# relays.net
KiCad netlist of a schematic drawn in EAGLE
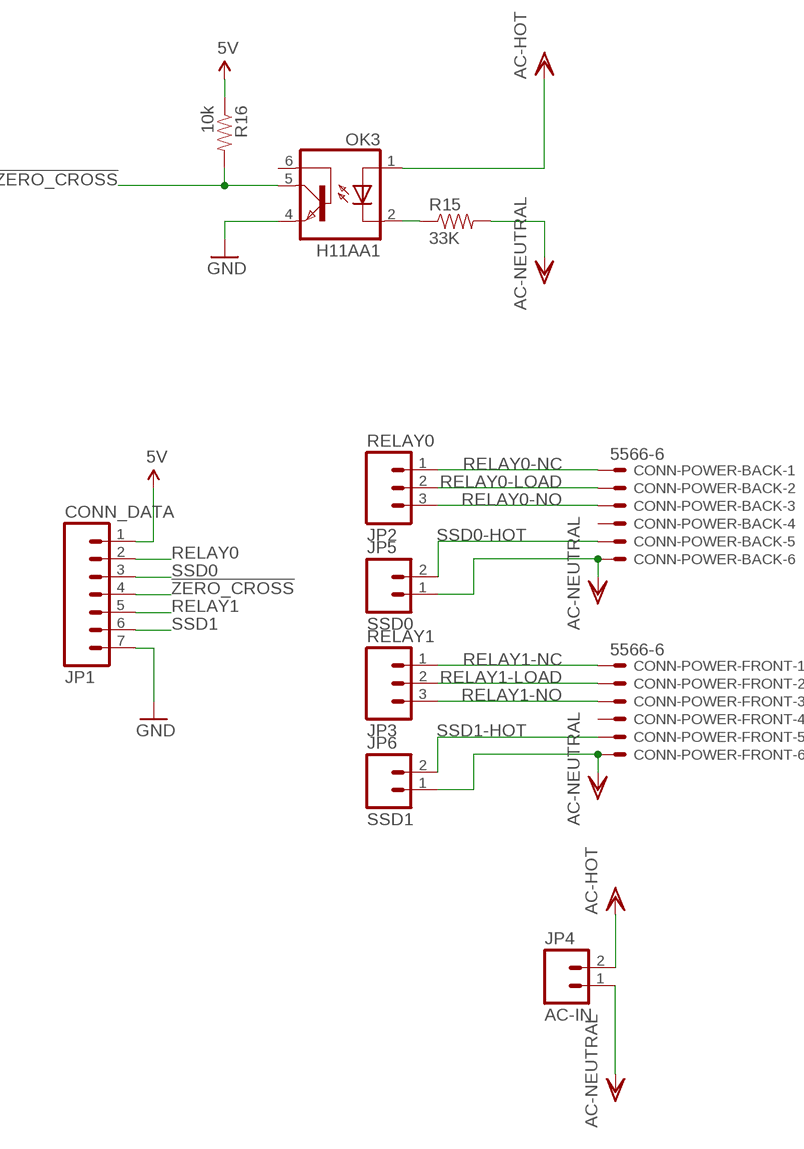
[diagram p0: schematic, sheet 1]
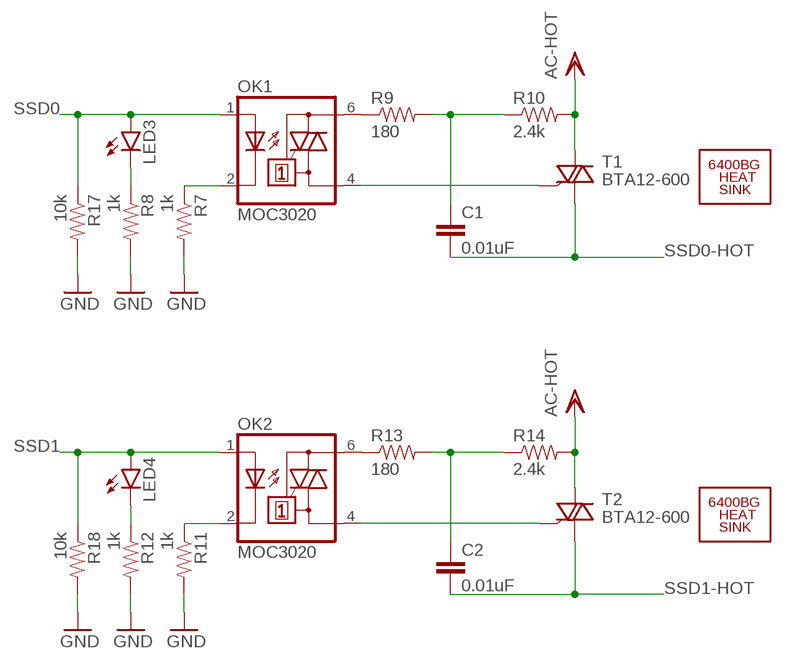
[diagram p1: schematic, sheet 2]
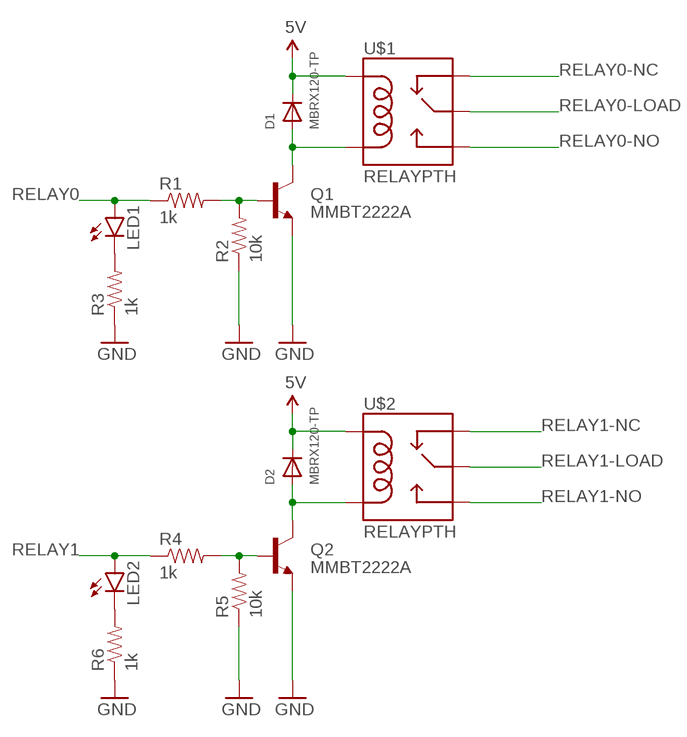
[diagram p2: schematic, sheet 3]

(export (version "E")
  (design (tool "Eeschema 10.0.6"))
  (components
    (comp (ref "CONN-POWER-BACK")
      (value "5566-6")
      (footprint "eagle-import:5566-6")
      (fields (field (name "MPN") "95566-61002"))
      (libsource (lib "eagle-import") (part "5566-6"))
    )
    (comp (ref "CONN-POWER-FRONT")
      (value "5566-6")
      (footprint "eagle-import:5566-6")
      (fields (field (name "MPN") "95566-61002"))
      (libsource (lib "eagle-import") (part "5566-6"))
    )
    (comp (ref "JP1")
      (value "CONN_DATA")
      (footprint "eagle-import:1X07_LONGPADS")
      (libsource (lib "eagle-import") (part "M07LONGPADS"))
    )
    (comp (ref "JP2")
      (value "RELAY0")
      (footprint "eagle-import:SCREWTERMINAL-5MM-3")
      (libsource (lib "eagle-import") (part "M03-SCREW-5MM"))
    )
    (comp (ref "JP3")
      (value "RELAY1")
      (footprint "eagle-import:SCREWTERMINAL-5MM-3")
      (libsource (lib "eagle-import") (part "M03-SCREW-5MM"))
    )
    (comp (ref "JP4")
      (value "AC-IN")
      (footprint "eagle-import:SCREWTERMINAL-5MM-2")
      (libsource (lib "eagle-import") (part "M025MM"))
    )
    (comp (ref "JP5")
      (value "SSD0")
      (footprint "eagle-import:SCREWTERMINAL-5MM-2")
      (libsource (lib "eagle-import") (part "M025MM"))
    )
    (comp (ref "JP6")
      (value "SSD1")
      (footprint "eagle-import:SCREWTERMINAL-5MM-2")
      (libsource (lib "eagle-import") (part "M025MM"))
    )
    (comp (ref "OK3")
      (value "H11AA1")
      (footprint "eagle-import:DIL6-SMD")
      (libsource (lib "eagle-import") (part "H11A?MS1"))
    )
    (comp (ref "R15")
      (value "33K")
      (footprint "eagle-import:0603-RES")
      (libsource (lib "eagle-import") (part "RESISTOR0603-RES"))
    )
    (comp (ref "R16")
      (value "10k")
      (footprint "eagle-import:0603-RES")
      (libsource (lib "eagle-import") (part "RESISTOR0603-RES"))
    )
    (comp (ref "D1")
      (value "MBRX120-TP")
      (footprint "eagle-import:SOD-123")
      (libsource (lib "eagle-import") (part "DIODESOD-123"))
    )
    (comp (ref "D2")
      (value "MBRX120-TP")
      (footprint "eagle-import:SOD-123")
      (libsource (lib "eagle-import") (part "DIODESOD-123"))
    )
    (comp (ref "LED1")
      (value "LED0603")
      (footprint "eagle-import:LED-0603")
      (libsource (lib "eagle-import") (part "LED0603"))
    )
    (comp (ref "LED2")
      (value "LED0603")
      (footprint "eagle-import:LED-0603")
      (libsource (lib "eagle-import") (part "LED0603"))
    )
    (comp (ref "Q1")
      (value "MMBT2222A")
      (footprint "eagle-import:SOT23-3")
      (libsource (lib "eagle-import") (part "TRANSISTOR_NPNMMBT2222A"))
    )
    (comp (ref "Q2")
      (value "MMBT2222A")
      (footprint "eagle-import:SOT23-3")
      (libsource (lib "eagle-import") (part "TRANSISTOR_NPNMMBT2222A"))
    )
    (comp (ref "R1")
      (value "1k")
      (footprint "eagle-import:0603-RES")
      (libsource (lib "eagle-import") (part "RESISTOR0603-RES"))
    )
    (comp (ref "R2")
      (value "10k")
      (footprint "eagle-import:0603-RES")
      (libsource (lib "eagle-import") (part "RESISTOR0603-RES"))
    )
    (comp (ref "R3")
      (value "1k")
      (footprint "eagle-import:0603-RES")
      (libsource (lib "eagle-import") (part "RESISTOR0603-RES"))
    )
    (comp (ref "R4")
      (value "1k")
      (footprint "eagle-import:0603-RES")
      (libsource (lib "eagle-import") (part "RESISTOR0603-RES"))
    )
    (comp (ref "R5")
      (value "10k")
      (footprint "eagle-import:0603-RES")
      (libsource (lib "eagle-import") (part "RESISTOR0603-RES"))
    )
    (comp (ref "R6")
      (value "1k")
      (footprint "eagle-import:0603-RES")
      (libsource (lib "eagle-import") (part "RESISTOR0603-RES"))
    )
    (comp (ref "U$1")
      (value "RELAYPTH")
      (footprint "eagle-import:RELAY-G5Q")
      (libsource (lib "eagle-import") (part "RELAYPTH"))
    )
    (comp (ref "U$2")
      (value "RELAYPTH")
      (footprint "eagle-import:RELAY-G5Q")
      (libsource (lib "eagle-import") (part "RELAYPTH"))
    )
    (comp (ref "C1")
      (value "0.01uF")
      (footprint "eagle-import:0603-CAP")
      (libsource (lib "eagle-import") (part "CAP0603-CAP"))
    )
    (comp (ref "C2")
      (value "0.01uF")
      (footprint "eagle-import:0603-CAP")
      (libsource (lib "eagle-import") (part "CAP0603-CAP"))
    )
    (comp (ref "LED3")
      (value "LED0603")
      (footprint "eagle-import:LED-0603")
      (libsource (lib "eagle-import") (part "LED0603"))
    )
    (comp (ref "LED4")
      (value "LED0603")
      (footprint "eagle-import:LED-0603")
      (libsource (lib "eagle-import") (part "LED0603"))
    )
    (comp (ref "OK1")
      (value "MOC3020")
      (footprint "eagle-import:DIL6-SMD")
      (fields (field (name "MF") "FAIRCHILD SEMICONDUCTOR") (field (name "MPN") "MOC3031SM"))
      (libsource (lib "eagle-import") (part "MOC30S31"))
    )
    (comp (ref "OK2")
      (value "MOC3020")
      (footprint "eagle-import:DIL6-SMD")
      (fields (field (name "MF") "FAIRCHILD SEMICONDUCTOR") (field (name "MPN") "MOC3031SM"))
      (libsource (lib "eagle-import") (part "MOC30S31"))
    )
    (comp (ref "R7")
      (value "1k")
      (footprint "eagle-import:0603-RES")
      (libsource (lib "eagle-import") (part "RESISTOR0603-RES"))
    )
    (comp (ref "R8")
      (value "1k")
      (footprint "eagle-import:0603-RES")
      (libsource (lib "eagle-import") (part "RESISTOR0603-RES"))
    )
    (comp (ref "R9")
      (value "180")
      (footprint "eagle-import:0603-RES")
      (libsource (lib "eagle-import") (part "RESISTOR0603-RES"))
    )
    (comp (ref "R10")
      (value "2.4k")
      (footprint "eagle-import:0603-RES")
      (libsource (lib "eagle-import") (part "RESISTOR0603-RES"))
    )
    (comp (ref "R11")
      (value "1k")
      (footprint "eagle-import:0603-RES")
      (libsource (lib "eagle-import") (part "RESISTOR0603-RES"))
    )
    (comp (ref "R12")
      (value "1k")
      (footprint "eagle-import:0603-RES")
      (libsource (lib "eagle-import") (part "RESISTOR0603-RES"))
    )
    (comp (ref "R13")
      (value "180")
      (footprint "eagle-import:0603-RES")
      (libsource (lib "eagle-import") (part "RESISTOR0603-RES"))
    )
    (comp (ref "R14")
      (value "2.4k")
      (footprint "eagle-import:0603-RES")
      (libsource (lib "eagle-import") (part "RESISTOR0603-RES"))
    )
    (comp (ref "R17")
      (value "10k")
      (footprint "eagle-import:0603-RES")
      (libsource (lib "eagle-import") (part "RESISTOR0603-RES"))
    )
    (comp (ref "R18")
      (value "10k")
      (footprint "eagle-import:0603-RES")
      (libsource (lib "eagle-import") (part "RESISTOR0603-RES"))
    )
    (comp (ref "T1")
      (value "BTA12-600")
      (footprint "eagle-import:TO220AB")
      (libsource (lib "eagle-import") (part "BT136"))
    )
    (comp (ref "T2")
      (value "BTA12-600")
      (footprint "eagle-import:TO220AB")
      (libsource (lib "eagle-import") (part "BT136"))
    )
    (comp (ref "U$3")
      (value "6400BG_HEATSINK")
      (footprint "eagle-import:6400BG_HEATSINK")
      (libsource (lib "eagle-import") (part "6400BG_HEATSINK"))
    )
    (comp (ref "U$4")
      (value "6400BG_HEATSINK")
      (footprint "eagle-import:6400BG_HEATSINK")
      (libsource (lib "eagle-import") (part "6400BG_HEATSINK"))
    )
  )
  (nets
    (net (code "1") (name "5V") (class "Default")
      (node (ref "D1") (pin "C") (pinfunction "C_C") (pintype "passive"))
      (node (ref "D2") (pin "C") (pinfunction "C_C") (pintype "passive"))
      (node (ref "JP1") (pin "1") (pinfunction "1_1") (pintype "passive"))
      (node (ref "R16") (pin "1") (pinfunction "1_1") (pintype "passive"))
      (node (ref "U$1") (pin "5") (pinfunction "COIL1_5") (pintype "bidirectional"))
      (node (ref "U$2") (pin "5") (pinfunction "COIL1_5") (pintype "bidirectional"))
    )
    (net (code "2") (name "AC-HOT") (class "Default")
      (node (ref "JP4") (pin "2") (pinfunction "2_2") (pintype "passive"))
      (node (ref "OK3") (pin "1") (pinfunction "A_1") (pintype "passive"))
      (node (ref "R10") (pin "2") (pinfunction "2_2") (pintype "passive"))
      (node (ref "R14") (pin "2") (pinfunction "2_2") (pintype "passive"))
      (node (ref "T1") (pin "2") (pinfunction "A2_2") (pintype "passive"))
      (node (ref "T2") (pin "2") (pinfunction "A2_2") (pintype "passive"))
    )
    (net (code "3") (name "AC-NEUTRAL") (class "Default")
      (node (ref "CONN-POWER-BACK") (pin "6") (pinfunction "S_6") (pintype "passive"))
      (node (ref "CONN-POWER-FRONT") (pin "6") (pinfunction "S_6") (pintype "passive"))
      (node (ref "JP4") (pin "1") (pinfunction "1_1") (pintype "passive"))
      (node (ref "JP5") (pin "1") (pinfunction "1_1") (pintype "passive"))
      (node (ref "JP6") (pin "1") (pinfunction "1_1") (pintype "passive"))
      (node (ref "R15") (pin "2") (pinfunction "2_2") (pintype "passive"))
    )
    (net (code "4") (name "GND") (class "Default")
      (node (ref "JP1") (pin "7") (pinfunction "7_7") (pintype "passive"))
      (node (ref "OK3") (pin "4") (pinfunction "EMI_4") (pintype "passive"))
      (node (ref "Q1") (pin "2") (pinfunction "E_2") (pintype "passive"))
      (node (ref "Q2") (pin "2") (pinfunction "E_2") (pintype "passive"))
      (node (ref "R11") (pin "2") (pinfunction "2_2") (pintype "passive"))
      (node (ref "R12") (pin "2") (pinfunction "2_2") (pintype "passive"))
      (node (ref "R17") (pin "2") (pinfunction "2_2") (pintype "passive"))
      (node (ref "R18") (pin "2") (pinfunction "2_2") (pintype "passive"))
      (node (ref "R2") (pin "1") (pinfunction "1_1") (pintype "passive"))
      (node (ref "R3") (pin "1") (pinfunction "1_1") (pintype "passive"))
      (node (ref "R5") (pin "1") (pinfunction "1_1") (pintype "passive"))
      (node (ref "R6") (pin "1") (pinfunction "1_1") (pintype "passive"))
      (node (ref "R7") (pin "2") (pinfunction "2_2") (pintype "passive"))
      (node (ref "R8") (pin "2") (pinfunction "2_2") (pintype "passive"))
    )
    (net (code "5") (name "Net-(C1-Pad1)") (class "Default")
      (node (ref "C1") (pin "1") (pinfunction "1_1") (pintype "passive"))
      (node (ref "R10") (pin "1") (pinfunction "1_1") (pintype "passive"))
      (node (ref "R9") (pin "2") (pinfunction "2_2") (pintype "passive"))
    )
    (net (code "6") (name "Net-(C2-Pad1)") (class "Default")
      (node (ref "C2") (pin "1") (pinfunction "1_1") (pintype "passive"))
      (node (ref "R13") (pin "2") (pinfunction "2_2") (pintype "passive"))
      (node (ref "R14") (pin "1") (pinfunction "1_1") (pintype "passive"))
    )
    (net (code "7") (name "Net-(LED1-PadC)") (class "Default")
      (node (ref "LED1") (pin "C") (pinfunction "C_C") (pintype "passive"))
      (node (ref "R3") (pin "2") (pinfunction "2_2") (pintype "passive"))
    )
    (net (code "8") (name "Net-(LED2-PadC)") (class "Default")
      (node (ref "LED2") (pin "C") (pinfunction "C_C") (pintype "passive"))
      (node (ref "R6") (pin "2") (pinfunction "2_2") (pintype "passive"))
    )
    (net (code "9") (name "Net-(LED3-PadC)") (class "Default")
      (node (ref "LED3") (pin "C") (pinfunction "C_C") (pintype "passive"))
      (node (ref "R8") (pin "1") (pinfunction "1_1") (pintype "passive"))
    )
    (net (code "10") (name "Net-(LED4-PadC)") (class "Default")
      (node (ref "LED4") (pin "C") (pinfunction "C_C") (pintype "passive"))
      (node (ref "R12") (pin "1") (pinfunction "1_1") (pintype "passive"))
    )
    (net (code "11") (name "Net-(OK1-A1)") (class "Default")
      (node (ref "OK1") (pin "4") (pinfunction "A1_4") (pintype "passive"))
      (node (ref "T1") (pin "3") (pinfunction "G_3") (pintype "passive"))
    )
    (net (code "12") (name "Net-(OK1-A2)") (class "Default")
      (node (ref "OK1") (pin "6") (pinfunction "A2_6") (pintype "passive"))
      (node (ref "R9") (pin "1") (pinfunction "1_1") (pintype "passive"))
    )
    (net (code "13") (name "Net-(OK1-C)") (class "Default")
      (node (ref "OK1") (pin "2") (pinfunction "C_2") (pintype "passive"))
      (node (ref "R7") (pin "1") (pinfunction "1_1") (pintype "passive"))
    )
    (net (code "14") (name "Net-(OK2-A1)") (class "Default")
      (node (ref "OK2") (pin "4") (pinfunction "A1_4") (pintype "passive"))
      (node (ref "T2") (pin "3") (pinfunction "G_3") (pintype "passive"))
    )
    (net (code "15") (name "Net-(OK2-A2)") (class "Default")
      (node (ref "OK2") (pin "6") (pinfunction "A2_6") (pintype "passive"))
      (node (ref "R13") (pin "1") (pinfunction "1_1") (pintype "passive"))
    )
    (net (code "16") (name "Net-(OK2-C)") (class "Default")
      (node (ref "OK2") (pin "2") (pinfunction "C_2") (pintype "passive"))
      (node (ref "R11") (pin "1") (pinfunction "1_1") (pintype "passive"))
    )
    (net (code "17") (name "Net-(OK3-C)") (class "Default")
      (node (ref "OK3") (pin "2") (pinfunction "C_2") (pintype "passive"))
      (node (ref "R15") (pin "1") (pinfunction "1_1") (pintype "passive"))
    )
    (net (code "18") (name "Net-(Q1-B)") (class "Default")
      (node (ref "Q1") (pin "1") (pinfunction "B_1") (pintype "passive"))
      (node (ref "R1") (pin "2") (pinfunction "2_2") (pintype "passive"))
      (node (ref "R2") (pin "2") (pinfunction "2_2") (pintype "passive"))
    )
    (net (code "19") (name "Net-(Q1-C)") (class "Default")
      (node (ref "D1") (pin "A") (pinfunction "A_A") (pintype "passive"))
      (node (ref "Q1") (pin "3") (pinfunction "C_3") (pintype "passive"))
      (node (ref "U$1") (pin "1") (pinfunction "COIL2_1") (pintype "bidirectional"))
    )
    (net (code "20") (name "Net-(Q2-B)") (class "Default")
      (node (ref "Q2") (pin "1") (pinfunction "B_1") (pintype "passive"))
      (node (ref "R4") (pin "2") (pinfunction "2_2") (pintype "passive"))
      (node (ref "R5") (pin "2") (pinfunction "2_2") (pintype "passive"))
    )
    (net (code "21") (name "Net-(Q2-C)") (class "Default")
      (node (ref "D2") (pin "A") (pinfunction "A_A") (pintype "passive"))
      (node (ref "Q2") (pin "3") (pinfunction "C_3") (pintype "passive"))
      (node (ref "U$2") (pin "1") (pinfunction "COIL2_1") (pintype "bidirectional"))
    )
    (net (code "22") (name "RELAY0") (class "Default")
      (node (ref "JP1") (pin "2") (pinfunction "2_2") (pintype "passive"))
      (node (ref "LED1") (pin "A") (pinfunction "A_A") (pintype "passive"))
      (node (ref "R1") (pin "1") (pinfunction "1_1") (pintype "passive"))
    )
    (net (code "23") (name "RELAY0-LOAD") (class "Default")
      (node (ref "CONN-POWER-BACK") (pin "2") (pinfunction "S_2") (pintype "passive"))
      (node (ref "JP2") (pin "2") (pinfunction "2_2") (pintype "passive"))
      (node (ref "U$1") (pin "2") (pinfunction "MAIN_2") (pintype "bidirectional"))
    )
    (net (code "24") (name "RELAY0-NC") (class "Default")
      (node (ref "CONN-POWER-BACK") (pin "1") (pinfunction "S_1") (pintype "passive"))
      (node (ref "JP2") (pin "1") (pinfunction "1_1") (pintype "passive"))
      (node (ref "U$1") (pin "4") (pinfunction "NC_4") (pintype "bidirectional"))
    )
    (net (code "25") (name "RELAY0-NO") (class "Default")
      (node (ref "CONN-POWER-BACK") (pin "3") (pinfunction "S_3") (pintype "passive"))
      (node (ref "JP2") (pin "3") (pinfunction "3_3") (pintype "passive"))
      (node (ref "U$1") (pin "3") (pinfunction "NO_3") (pintype "bidirectional"))
    )
    (net (code "26") (name "RELAY1") (class "Default")
      (node (ref "JP1") (pin "5") (pinfunction "5_5") (pintype "passive"))
      (node (ref "LED2") (pin "A") (pinfunction "A_A") (pintype "passive"))
      (node (ref "R4") (pin "1") (pinfunction "1_1") (pintype "passive"))
    )
    (net (code "27") (name "RELAY1-LOAD") (class "Default")
      (node (ref "CONN-POWER-FRONT") (pin "2") (pinfunction "S_2") (pintype "passive"))
      (node (ref "JP3") (pin "2") (pinfunction "2_2") (pintype "passive"))
      (node (ref "U$2") (pin "2") (pinfunction "MAIN_2") (pintype "bidirectional"))
    )
    (net (code "28") (name "RELAY1-NC") (class "Default")
      (node (ref "CONN-POWER-FRONT") (pin "1") (pinfunction "S_1") (pintype "passive"))
      (node (ref "JP3") (pin "1") (pinfunction "1_1") (pintype "passive"))
      (node (ref "U$2") (pin "4") (pinfunction "NC_4") (pintype "bidirectional"))
    )
    (net (code "29") (name "RELAY1-NO") (class "Default")
      (node (ref "CONN-POWER-FRONT") (pin "3") (pinfunction "S_3") (pintype "passive"))
      (node (ref "JP3") (pin "3") (pinfunction "3_3") (pintype "passive"))
      (node (ref "U$2") (pin "3") (pinfunction "NO_3") (pintype "bidirectional"))
    )
    (net (code "30") (name "SSD0") (class "Default")
      (node (ref "JP1") (pin "3") (pinfunction "3_3") (pintype "passive"))
      (node (ref "LED3") (pin "A") (pinfunction "A_A") (pintype "passive"))
      (node (ref "OK1") (pin "1") (pinfunction "A_1") (pintype "passive"))
      (node (ref "R17") (pin "1") (pinfunction "1_1") (pintype "passive"))
    )
    (net (code "31") (name "SSD0-HOT") (class "Default")
      (node (ref "C1") (pin "2") (pinfunction "2_2") (pintype "passive"))
      (node (ref "CONN-POWER-BACK") (pin "5") (pinfunction "S_5") (pintype "passive"))
      (node (ref "JP5") (pin "2") (pinfunction "2_2") (pintype "passive"))
      (node (ref "T1") (pin "1") (pinfunction "A1_1") (pintype "passive"))
    )
    (net (code "32") (name "SSD1") (class "Default")
      (node (ref "JP1") (pin "6") (pinfunction "6_6") (pintype "passive"))
      (node (ref "LED4") (pin "A") (pinfunction "A_A") (pintype "passive"))
      (node (ref "OK2") (pin "1") (pinfunction "A_1") (pintype "passive"))
      (node (ref "R18") (pin "1") (pinfunction "1_1") (pintype "passive"))
    )
    (net (code "33") (name "SSD1-HOT") (class "Default")
      (node (ref "C2") (pin "2") (pinfunction "2_2") (pintype "passive"))
      (node (ref "CONN-POWER-FRONT") (pin "5") (pinfunction "S_5") (pintype "passive"))
      (node (ref "JP6") (pin "2") (pinfunction "2_2") (pintype "passive"))
      (node (ref "T2") (pin "1") (pinfunction "A1_1") (pintype "passive"))
    )
    (net (code "34") (name "unconnected-(CONN-POWER-BACKD-S-Pad4)") (class "Default")
      (node (ref "CONN-POWER-BACK") (pin "4") (pinfunction "S_4") (pintype "passive"))
    )
    (net (code "35") (name "unconnected-(CONN-POWER-FRONTD-S-Pad4)") (class "Default")
      (node (ref "CONN-POWER-FRONT") (pin "4") (pinfunction "S_4") (pintype "passive"))
    )
    (net (code "36") (name "unconnected-(OK3-BAS-Pad6)") (class "Default")
      (node (ref "OK3") (pin "6") (pinfunction "BAS_6") (pintype "passive"))
    )
    (net (code "37") (name "~{ZERO_CROSS}") (class "Default")
      (node (ref "JP1") (pin "4") (pinfunction "4_4") (pintype "passive"))
      (node (ref "OK3") (pin "5") (pinfunction "COL_5") (pintype "passive"))
      (node (ref "R16") (pin "2") (pinfunction "2_2") (pintype "passive"))
    )
  )
)
